# ST_Link_v2_1.net
KiCad netlist of a schematic drawn in EasyEDA Pro
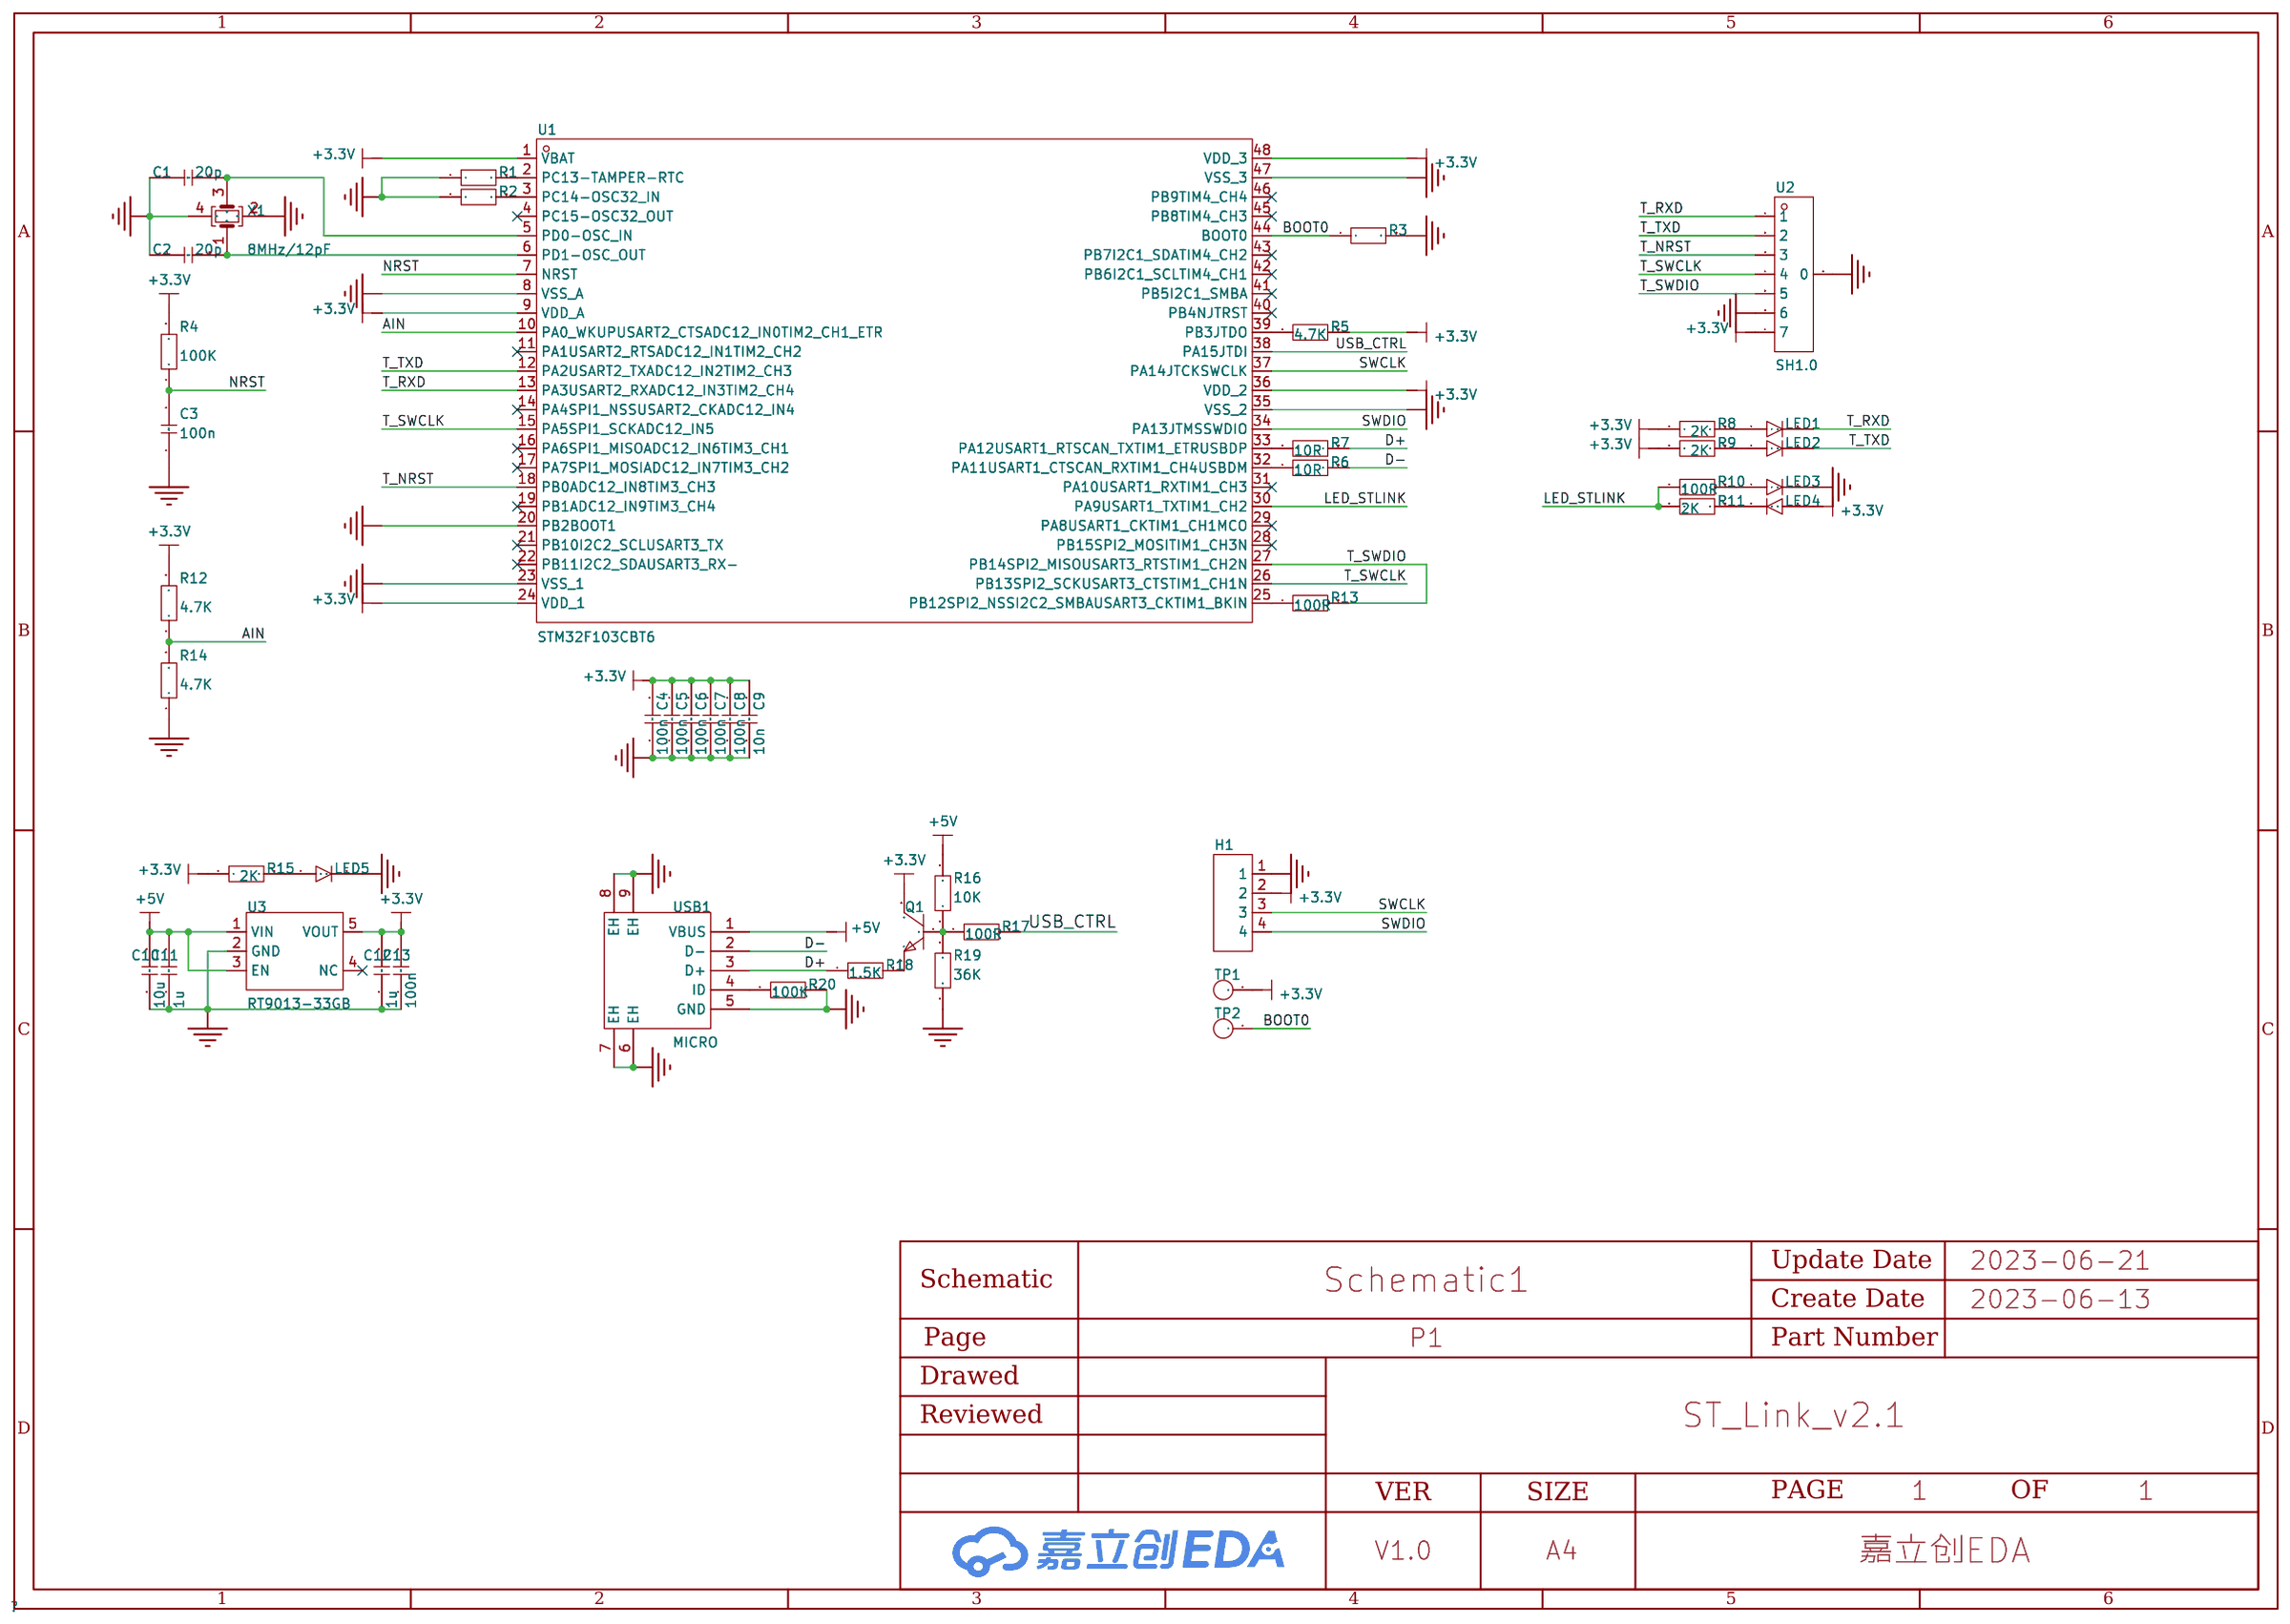
[diagram p0: schematic sheet]

(export (version "E")
  (design (tool "Eeschema 10.0.6"))
  (components
    (comp (ref "C1")
      (value "20p")
      (footprint "easyedapro:C0402")
      (libsource (lib "easyedapro") (part "C0402"))
    )
    (comp (ref "C2")
      (value "20p")
      (footprint "easyedapro:C0402")
      (libsource (lib "easyedapro") (part "C0402"))
    )
    (comp (ref "C3")
      (value "100n")
      (footprint "easyedapro:C0402")
      (libsource (lib "easyedapro") (part "C0402"))
    )
    (comp (ref "C4")
      (value "100n")
      (footprint "easyedapro:C0402")
      (libsource (lib "easyedapro") (part "C0402"))
    )
    (comp (ref "C5")
      (value "100n")
      (footprint "easyedapro:C0402")
      (libsource (lib "easyedapro") (part "C0402"))
    )
    (comp (ref "C6")
      (value "100n")
      (footprint "easyedapro:C0402")
      (libsource (lib "easyedapro") (part "C0402"))
    )
    (comp (ref "C7")
      (value "100n")
      (footprint "easyedapro:C0402")
      (libsource (lib "easyedapro") (part "C0402"))
    )
    (comp (ref "C8")
      (value "100n")
      (footprint "easyedapro:C0402")
      (libsource (lib "easyedapro") (part "C0402"))
    )
    (comp (ref "C9")
      (value "10n")
      (footprint "easyedapro:C0402")
      (libsource (lib "easyedapro") (part "C0402"))
    )
    (comp (ref "C10")
      (value "10u")
      (footprint "easyedapro:C0402")
      (libsource (lib "easyedapro") (part "C0402"))
    )
    (comp (ref "C11")
      (value "1u")
      (footprint "easyedapro:C0402")
      (libsource (lib "easyedapro") (part "C0402"))
    )
    (comp (ref "C12")
      (value "1u")
      (footprint "easyedapro:C0402")
      (libsource (lib "easyedapro") (part "C0402"))
    )
    (comp (ref "C13")
      (value "100n")
      (footprint "easyedapro:C0402")
      (libsource (lib "easyedapro") (part "C0402"))
    )
    (comp (ref "H1")
      (value "~")
      (footprint "easyedapro:PIN_1.27_1x4")
      (libsource (lib "easyedapro") (part "PIN_1.27_1x4"))
    )
    (comp (ref "LED1")
      (value "red")
      (footprint "easyedapro:LED0402")
      (libsource (lib "easyedapro") (part "LED-R-0402"))
    )
    (comp (ref "LED2")
      (value "green")
      (footprint "easyedapro:LED0402")
      (libsource (lib "easyedapro") (part "LED-G-0402"))
    )
    (comp (ref "LED3")
      (value "red")
      (footprint "easyedapro:LED0402")
      (libsource (lib "easyedapro") (part "LED-R-0402"))
    )
    (comp (ref "LED4")
      (value "green")
      (footprint "easyedapro:LED0402")
      (libsource (lib "easyedapro") (part "LED-G-0402"))
    )
    (comp (ref "LED5")
      (value "red")
      (footprint "easyedapro:LED0402")
      (libsource (lib "easyedapro") (part "LED-R-0402"))
    )
    (comp (ref "Q1")
      (value "~")
      (footprint "easyedapro:S8050_SOT-23")
      (libsource (lib "easyedapro") (part "NPN"))
    )
    (comp (ref "R1")
      (value "10K")
      (footprint "easyedapro:R0402")
      (libsource (lib "easyedapro") (part "R0402"))
    )
    (comp (ref "R2")
      (value "10K")
      (footprint "easyedapro:R0402")
      (libsource (lib "easyedapro") (part "R0402"))
    )
    (comp (ref "R3")
      (value "10K")
      (footprint "easyedapro:R0402")
      (libsource (lib "easyedapro") (part "R0402"))
    )
    (comp (ref "R4")
      (value "100K")
      (footprint "easyedapro:R0402")
      (libsource (lib "easyedapro") (part "R0402"))
    )
    (comp (ref "R5")
      (value "4.7K")
      (footprint "easyedapro:R0402")
      (libsource (lib "easyedapro") (part "R0402"))
    )
    (comp (ref "R6")
      (value "10R")
      (footprint "easyedapro:R0402")
      (libsource (lib "easyedapro") (part "R0402"))
    )
    (comp (ref "R7")
      (value "10R")
      (footprint "easyedapro:R0402")
      (libsource (lib "easyedapro") (part "R0402"))
    )
    (comp (ref "R8")
      (value "2K")
      (footprint "easyedapro:R0402")
      (libsource (lib "easyedapro") (part "R0402"))
    )
    (comp (ref "R9")
      (value "2K")
      (footprint "easyedapro:R0402")
      (libsource (lib "easyedapro") (part "R0402"))
    )
    (comp (ref "R10")
      (value "100R")
      (footprint "easyedapro:R0402")
      (libsource (lib "easyedapro") (part "R0402"))
    )
    (comp (ref "R11")
      (value "2K")
      (footprint "easyedapro:R0402")
      (libsource (lib "easyedapro") (part "R0402"))
    )
    (comp (ref "R12")
      (value "4.7K")
      (footprint "easyedapro:R0402")
      (libsource (lib "easyedapro") (part "R0402"))
    )
    (comp (ref "R13")
      (value "100R")
      (footprint "easyedapro:R0402")
      (libsource (lib "easyedapro") (part "R0402"))
    )
    (comp (ref "R14")
      (value "4.7K")
      (footprint "easyedapro:R0402")
      (libsource (lib "easyedapro") (part "R0402"))
    )
    (comp (ref "R15")
      (value "2K")
      (footprint "easyedapro:R0402")
      (libsource (lib "easyedapro") (part "R0402"))
    )
    (comp (ref "R16")
      (value "10K")
      (footprint "easyedapro:R0402")
      (libsource (lib "easyedapro") (part "R0402"))
    )
    (comp (ref "R17")
      (value "100R")
      (footprint "easyedapro:R0402")
      (libsource (lib "easyedapro") (part "R0402"))
    )
    (comp (ref "R18")
      (value "1.5K")
      (footprint "easyedapro:R0402")
      (libsource (lib "easyedapro") (part "R0402"))
    )
    (comp (ref "R19")
      (value "36K")
      (footprint "easyedapro:R0402")
      (libsource (lib "easyedapro") (part "R0402"))
    )
    (comp (ref "R20")
      (value "100K")
      (footprint "easyedapro:R0402")
      (libsource (lib "easyedapro") (part "R0402"))
    )
    (comp (ref "TP1")
      (value "~")
      (footprint "easyedapro:TP-1.27")
      (libsource (lib "easyedapro") (part "TP-1.27"))
    )
    (comp (ref "TP2")
      (value "~")
      (footprint "easyedapro:TP-1.27")
      (libsource (lib "easyedapro") (part "TP-1.27"))
    )
    (comp (ref "U1")
      (value "STM32F103CBT6")
      (footprint "easyedapro:LQFP-48_L7.0-W7.0-P0.50-LS9.0-BL")
      (fields (field (name "Manufacturer") "ST(意法半导体)"))
      (libsource (lib "easyedapro") (part "STM32F103CBT6"))
    )
    (comp (ref "U2")
      (value "SH1.0")
      (footprint "easyedapro:CONN-SMD_7P-SH1.00-7P-WT")
      (libsource (lib "easyedapro") (part "SH1.0_7P"))
    )
    (comp (ref "U3")
      (value "RT9013-33GB")
      (footprint "easyedapro:SOT-23-5_L3.0-W1.7-P0.95-LS2.8-BL")
      (description "输出类型:固定;输出极性:正;最大输入电压:5.5V;输出电压:3.3V;输出电流:500mA;电源纹波抑制比(PSRR):50dB@(10kHz);")
      (fields (field (name "Manufacturer") "RICHTEK(立锜)"))
      (libsource (lib "easyedapro") (part "RT9013-33GB"))
    )
    (comp (ref "USB1")
      (value "MICRO")
      (footprint "easyedapro:MICRO-USB-SMD_KH-MICRO-SMT.J7.2-5P")
      (description "连接器类型:Micro-B;标准:USB 2.0;公母:母座;触点数量:5;端口数量:1;安装方式:卧贴;额定电流 - 电源:1A;工作温度范围:-30°C~+80°C;")
      (fields (field (name "Manufacturer") "kinghelm(金航标)"))
      (libsource (lib "easyedapro") (part "KH-MICRO-SMT.J7.2-5P"))
    )
    (comp (ref "X1")
      (value "8MHz/12pF")
      (footprint "easyedapro:OSC-SMD_4P-L3.2-W2.5-BL")
      (fields (field (name "Manufacturer Part") "X322516MLB4SI") (field (name "Manufacturer") "YXC(扬兴晶振)"))
      (libsource (lib "easyedapro") (part "OSC3225"))
    )
  )
  (nets
    (net (code "1") (name "+3.3V") (class "Default")
      (node (ref "C12") (pin "2") (pinfunction "2_2") (pintype "input"))
      (node (ref "C13") (pin "2") (pinfunction "2_2") (pintype "input"))
      (node (ref "C4") (pin "2") (pinfunction "2_2") (pintype "input"))
      (node (ref "C5") (pin "2") (pinfunction "2_2") (pintype "input"))
      (node (ref "C6") (pin "2") (pinfunction "2_2") (pintype "input"))
      (node (ref "C7") (pin "2") (pinfunction "2_2") (pintype "input"))
      (node (ref "C8") (pin "2") (pinfunction "2_2") (pintype "input"))
      (node (ref "C9") (pin "2") (pinfunction "2_2") (pintype "input"))
      (node (ref "H1") (pin "2") (pinfunction "2_2") (pintype "input"))
      (node (ref "LED4") (pin "1") (pinfunction "1_1") (pintype "input"))
      (node (ref "Q1") (pin "3") (pinfunction "3_3") (pintype "unspecified"))
      (node (ref "R12") (pin "2") (pinfunction "2_2") (pintype "input"))
      (node (ref "R15") (pin "1") (pinfunction "1_1") (pintype "input"))
      (node (ref "R4") (pin "2") (pinfunction "2_2") (pintype "input"))
      (node (ref "R5") (pin "2") (pinfunction "2_2") (pintype "input"))
      (node (ref "R8") (pin "1") (pinfunction "1_1") (pintype "input"))
      (node (ref "R9") (pin "1") (pinfunction "1_1") (pintype "input"))
      (node (ref "TP1") (pin "1") (pinfunction "1_1") (pintype "input"))
      (node (ref "U1") (pin "1") (pinfunction "VBAT_1") (pintype "input"))
      (node (ref "U1") (pin "24") (pinfunction "VDD_1_24") (pintype "input"))
      (node (ref "U1") (pin "36") (pinfunction "VDD_2_36") (pintype "input"))
      (node (ref "U1") (pin "48") (pinfunction "VDD_3_48") (pintype "input"))
      (node (ref "U1") (pin "9") (pinfunction "VDD_A_9") (pintype "input"))
      (node (ref "U2") (pin "7") (pinfunction "7_7") (pintype "input"))
      (node (ref "U3") (pin "5") (pinfunction "VOUT_5") (pintype "input"))
    )
    (net (code "2") (name "+5V") (class "Default")
      (node (ref "C10") (pin "2") (pinfunction "2_2") (pintype "input"))
      (node (ref "C11") (pin "2") (pinfunction "2_2") (pintype "input"))
      (node (ref "R16") (pin "2") (pinfunction "2_2") (pintype "input"))
      (node (ref "U3") (pin "1") (pinfunction "VIN_1") (pintype "input"))
      (node (ref "U3") (pin "3") (pinfunction "EN_3") (pintype "input"))
      (node (ref "USB1") (pin "1") (pinfunction "VBUS_1") (pintype "input"))
    )
    (net (code "3") (name "/AIN") (class "Default")
      (node (ref "R12") (pin "1") (pinfunction "1_1") (pintype "input"))
      (node (ref "R14") (pin "2") (pinfunction "2_2") (pintype "input"))
      (node (ref "U1") (pin "10") (pinfunction "PA0_WKUPUSART2_CTSADC12_IN0TIM2_CH1_ETR_10") (pintype "input"))
    )
    (net (code "4") (name "/BOOT0") (class "Default")
      (node (ref "R3") (pin "1") (pinfunction "1_1") (pintype "input"))
      (node (ref "TP2") (pin "1") (pinfunction "1_1") (pintype "input"))
      (node (ref "U1") (pin "44") (pinfunction "BOOT0_44") (pintype "input"))
    )
    (net (code "5") (name "/D+") (class "Default")
      (node (ref "R18") (pin "1") (pinfunction "1_1") (pintype "input"))
      (node (ref "R7") (pin "2") (pinfunction "2_2") (pintype "input"))
      (node (ref "USB1") (pin "3") (pinfunction "D+_3") (pintype "input"))
    )
    (net (code "6") (name "/D-") (class "Default")
      (node (ref "R6") (pin "2") (pinfunction "2_2") (pintype "input"))
      (node (ref "USB1") (pin "2") (pinfunction "D-_2") (pintype "input"))
    )
    (net (code "7") (name "/LED_STLINK") (class "Default")
      (node (ref "R10") (pin "1") (pinfunction "1_1") (pintype "input"))
      (node (ref "R11") (pin "1") (pinfunction "1_1") (pintype "input"))
      (node (ref "U1") (pin "30") (pinfunction "PA9USART1_TXTIM1_CH2_30") (pintype "input"))
    )
    (net (code "8") (name "/NRST") (class "Default")
      (node (ref "C3") (pin "2") (pinfunction "2_2") (pintype "input"))
      (node (ref "R4") (pin "1") (pinfunction "1_1") (pintype "input"))
      (node (ref "U1") (pin "7") (pinfunction "NRST_7") (pintype "input"))
    )
    (net (code "9") (name "/SWCLK") (class "Default")
      (node (ref "H1") (pin "3") (pinfunction "3_3") (pintype "input"))
      (node (ref "U1") (pin "37") (pinfunction "PA14JTCKSWCLK_37") (pintype "input"))
    )
    (net (code "10") (name "/SWDIO") (class "Default")
      (node (ref "H1") (pin "4") (pinfunction "4_4") (pintype "input"))
      (node (ref "U1") (pin "34") (pinfunction "PA13JTMSSWDIO_34") (pintype "input"))
    )
    (net (code "11") (name "/T_NRST") (class "Default")
      (node (ref "U1") (pin "18") (pinfunction "PB0ADC12_IN8TIM3_CH3_18") (pintype "input"))
      (node (ref "U2") (pin "3") (pinfunction "3_3") (pintype "input"))
    )
    (net (code "12") (name "/T_RXD") (class "Default")
      (node (ref "LED1") (pin "2") (pinfunction "2_2") (pintype "input"))
      (node (ref "U1") (pin "13") (pinfunction "PA3USART2_RXADC12_IN3TIM2_CH4_13") (pintype "input"))
      (node (ref "U2") (pin "1") (pinfunction "1_1") (pintype "input"))
    )
    (net (code "13") (name "/T_SWCLK") (class "Default")
      (node (ref "U1") (pin "15") (pinfunction "PA5SPI1_SCKADC12_IN5_15") (pintype "input"))
      (node (ref "U1") (pin "26") (pinfunction "PB13SPI2_SCKUSART3_CTSTIM1_CH1N_26") (pintype "input"))
      (node (ref "U2") (pin "4") (pinfunction "4_4") (pintype "input"))
    )
    (net (code "14") (name "/T_SWDIO") (class "Default")
      (node (ref "R13") (pin "2") (pinfunction "2_2") (pintype "input"))
      (node (ref "U1") (pin "27") (pinfunction "PB14SPI2_MISOUSART3_RTSTIM1_CH2N_27") (pintype "input"))
      (node (ref "U2") (pin "5") (pinfunction "5_5") (pintype "input"))
    )
    (net (code "15") (name "/T_TXD") (class "Default")
      (node (ref "LED2") (pin "2") (pinfunction "2_2") (pintype "input"))
      (node (ref "U1") (pin "12") (pinfunction "PA2USART2_TXADC12_IN2TIM2_CH3_12") (pintype "input"))
      (node (ref "U2") (pin "2") (pinfunction "2_2") (pintype "input"))
    )
    (net (code "16") (name "/USB_CTRL") (class "Default")
      (node (ref "R17") (pin "2") (pinfunction "2_2") (pintype "input"))
      (node (ref "U1") (pin "38") (pinfunction "PA15JTDI_38") (pintype "input"))
    )
    (net (code "17") (name "GND") (class "Default")
      (node (ref "C1") (pin "1") (pinfunction "1_1") (pintype "input"))
      (node (ref "C10") (pin "1") (pinfunction "1_1") (pintype "input"))
      (node (ref "C11") (pin "1") (pinfunction "1_1") (pintype "input"))
      (node (ref "C12") (pin "1") (pinfunction "1_1") (pintype "input"))
      (node (ref "C13") (pin "1") (pinfunction "1_1") (pintype "input"))
      (node (ref "C2") (pin "1") (pinfunction "1_1") (pintype "input"))
      (node (ref "C3") (pin "1") (pinfunction "1_1") (pintype "input"))
      (node (ref "C4") (pin "1") (pinfunction "1_1") (pintype "input"))
      (node (ref "C5") (pin "1") (pinfunction "1_1") (pintype "input"))
      (node (ref "C6") (pin "1") (pinfunction "1_1") (pintype "input"))
      (node (ref "C7") (pin "1") (pinfunction "1_1") (pintype "input"))
      (node (ref "C8") (pin "1") (pinfunction "1_1") (pintype "input"))
      (node (ref "C9") (pin "1") (pinfunction "1_1") (pintype "input"))
      (node (ref "H1") (pin "1") (pinfunction "1_1") (pintype "input"))
      (node (ref "LED3") (pin "2") (pinfunction "2_2") (pintype "input"))
      (node (ref "LED5") (pin "2") (pinfunction "2_2") (pintype "input"))
      (node (ref "R1") (pin "1") (pinfunction "1_1") (pintype "input"))
      (node (ref "R14") (pin "1") (pinfunction "1_1") (pintype "input"))
      (node (ref "R19") (pin "1") (pinfunction "1_1") (pintype "input"))
      (node (ref "R2") (pin "1") (pinfunction "1_1") (pintype "input"))
      (node (ref "R20") (pin "2") (pinfunction "2_2") (pintype "input"))
      (node (ref "R3") (pin "2") (pinfunction "2_2") (pintype "input"))
      (node (ref "U1") (pin "20") (pinfunction "PB2BOOT1_20") (pintype "input"))
      (node (ref "U1") (pin "23") (pinfunction "VSS_1_23") (pintype "input"))
      (node (ref "U1") (pin "35") (pinfunction "VSS_2_35") (pintype "input"))
      (node (ref "U1") (pin "47") (pinfunction "VSS_3_47") (pintype "input"))
      (node (ref "U1") (pin "8") (pinfunction "VSS_A_8") (pintype "input"))
      (node (ref "U2") (pin "0") (pinfunction "0_0") (pintype "input"))
      (node (ref "U2") (pin "6") (pinfunction "6_6") (pintype "input"))
      (node (ref "U3") (pin "2") (pinfunction "GND_2") (pintype "input"))
      (node (ref "USB1") (pin "5") (pinfunction "GND_5") (pintype "input"))
      (node (ref "USB1") (pin "6") (pinfunction "EH_6") (pintype "input"))
      (node (ref "USB1") (pin "7") (pinfunction "EH_7") (pintype "input"))
      (node (ref "USB1") (pin "8") (pinfunction "EH_8") (pintype "input"))
      (node (ref "USB1") (pin "9") (pinfunction "EH_9") (pintype "input"))
      (node (ref "X1") (pin "2") (pinfunction "GND_2") (pintype "input"))
      (node (ref "X1") (pin "4") (pinfunction "GND_4") (pintype "input"))
    )
    (net (code "18") (name "Net-(LED1-Pad1)") (class "Default")
      (node (ref "LED1") (pin "1") (pinfunction "1_1") (pintype "input"))
      (node (ref "R8") (pin "2") (pinfunction "2_2") (pintype "input"))
    )
    (net (code "19") (name "Net-(LED2-Pad1)") (class "Default")
      (node (ref "LED2") (pin "1") (pinfunction "1_1") (pintype "input"))
      (node (ref "R9") (pin "2") (pinfunction "2_2") (pintype "input"))
    )
    (net (code "20") (name "Net-(LED3-Pad1)") (class "Default")
      (node (ref "LED3") (pin "1") (pinfunction "1_1") (pintype "input"))
      (node (ref "R10") (pin "2") (pinfunction "2_2") (pintype "input"))
    )
    (net (code "21") (name "Net-(LED4-Pad2)") (class "Default")
      (node (ref "LED4") (pin "2") (pinfunction "2_2") (pintype "input"))
      (node (ref "R11") (pin "2") (pinfunction "2_2") (pintype "input"))
    )
    (net (code "22") (name "Net-(LED5-Pad1)") (class "Default")
      (node (ref "LED5") (pin "1") (pinfunction "1_1") (pintype "input"))
      (node (ref "R15") (pin "2") (pinfunction "2_2") (pintype "input"))
    )
    (net (code "23") (name "Net-(Q1-Pad1)") (class "Default")
      (node (ref "Q1") (pin "1") (pinfunction "1_1") (pintype "unspecified"))
      (node (ref "R16") (pin "1") (pinfunction "1_1") (pintype "input"))
      (node (ref "R17") (pin "1") (pinfunction "1_1") (pintype "input"))
      (node (ref "R19") (pin "2") (pinfunction "2_2") (pintype "input"))
    )
    (net (code "24") (name "Net-(Q1-Pad2)") (class "Default")
      (node (ref "Q1") (pin "2") (pinfunction "2_2") (pintype "unspecified"))
      (node (ref "R18") (pin "2") (pinfunction "2_2") (pintype "input"))
    )
    (net (code "25") (name "Net-(U1-PA11USART1_CTSCAN_RXTIM1_CH4USBDM)") (class "Default")
      (node (ref "R6") (pin "1") (pinfunction "1_1") (pintype "input"))
      (node (ref "U1") (pin "32") (pinfunction "PA11USART1_CTSCAN_RXTIM1_CH4USBDM_32") (pintype "input"))
    )
    (net (code "26") (name "Net-(U1-PA12USART1_RTSCAN_TXTIM1_ETRUSBDP)") (class "Default")
      (node (ref "R7") (pin "1") (pinfunction "1_1") (pintype "input"))
      (node (ref "U1") (pin "33") (pinfunction "PA12USART1_RTSCAN_TXTIM1_ETRUSBDP_33") (pintype "input"))
    )
    (net (code "27") (name "Net-(U1-PB3JTDO)") (class "Default")
      (node (ref "R5") (pin "1") (pinfunction "1_1") (pintype "input"))
      (node (ref "U1") (pin "39") (pinfunction "PB3JTDO_39") (pintype "input"))
    )
    (net (code "28") (name "Net-(U1-PB12SPI2_NSSI2C2_SMBAUSART3_CKTIM1_BKIN)") (class "Default")
      (node (ref "R13") (pin "1") (pinfunction "1_1") (pintype "input"))
      (node (ref "U1") (pin "25") (pinfunction "PB12SPI2_NSSI2C2_SMBAUSART3_CKTIM1_BKIN_25") (pintype "input"))
    )
    (net (code "29") (name "Net-(U1-PC13-TAMPER-RTC)") (class "Default")
      (node (ref "R1") (pin "2") (pinfunction "2_2") (pintype "input"))
      (node (ref "U1") (pin "2") (pinfunction "PC13-TAMPER-RTC_2") (pintype "input"))
    )
    (net (code "30") (name "Net-(U1-PC14-OSC32_IN)") (class "Default")
      (node (ref "R2") (pin "2") (pinfunction "2_2") (pintype "input"))
      (node (ref "U1") (pin "3") (pinfunction "PC14-OSC32_IN_3") (pintype "input"))
    )
    (net (code "31") (name "Net-(U1-PD0-OSC_IN)") (class "Default")
      (node (ref "C1") (pin "2") (pinfunction "2_2") (pintype "input"))
      (node (ref "U1") (pin "5") (pinfunction "PD0-OSC_IN_5") (pintype "input"))
      (node (ref "X1") (pin "3") (pinfunction "OSC2_3") (pintype "input"))
    )
    (net (code "32") (name "Net-(U1-PD1-OSC_OUT)") (class "Default")
      (node (ref "C2") (pin "2") (pinfunction "2_2") (pintype "input"))
      (node (ref "U1") (pin "6") (pinfunction "PD1-OSC_OUT_6") (pintype "input"))
      (node (ref "X1") (pin "1") (pinfunction "OSC1_1") (pintype "input"))
    )
    (net (code "33") (name "Net-(USB1-ID)") (class "Default")
      (node (ref "R20") (pin "1") (pinfunction "1_1") (pintype "input"))
      (node (ref "USB1") (pin "4") (pinfunction "ID_4") (pintype "input"))
    )
    (net (code "34") (name "unconnected-(U1-PA1USART2_RTSADC12_IN1TIM2_CH2-Pad11)") (class "Default")
      (node (ref "U1") (pin "11") (pinfunction "PA1USART2_RTSADC12_IN1TIM2_CH2_11") (pintype "input+no_connect"))
    )
    (net (code "35") (name "unconnected-(U1-PA4SPI1_NSSUSART2_CKADC12_IN4-Pad14)") (class "Default")
      (node (ref "U1") (pin "14") (pinfunction "PA4SPI1_NSSUSART2_CKADC12_IN4_14") (pintype "input+no_connect"))
    )
    (net (code "36") (name "unconnected-(U1-PA6SPI1_MISOADC12_IN6TIM3_CH1-Pad16)") (class "Default")
      (node (ref "U1") (pin "16") (pinfunction "PA6SPI1_MISOADC12_IN6TIM3_CH1_16") (pintype "input+no_connect"))
    )
    (net (code "37") (name "unconnected-(U1-PA7SPI1_MOSIADC12_IN7TIM3_CH2-Pad17)") (class "Default")
      (node (ref "U1") (pin "17") (pinfunction "PA7SPI1_MOSIADC12_IN7TIM3_CH2_17") (pintype "input+no_connect"))
    )
    (net (code "38") (name "unconnected-(U1-PA8USART1_CKTIM1_CH1MCO-Pad29)") (class "Default")
      (node (ref "U1") (pin "29") (pinfunction "PA8USART1_CKTIM1_CH1MCO_29") (pintype "input+no_connect"))
    )
    (net (code "39") (name "unconnected-(U1-PA10USART1_RXTIM1_CH3-Pad31)") (class "Default")
      (node (ref "U1") (pin "31") (pinfunction "PA10USART1_RXTIM1_CH3_31") (pintype "input+no_connect"))
    )
    (net (code "40") (name "unconnected-(U1-PB1ADC12_IN9TIM3_CH4-Pad19)") (class "Default")
      (node (ref "U1") (pin "19") (pinfunction "PB1ADC12_IN9TIM3_CH4_19") (pintype "input+no_connect"))
    )
    (net (code "41") (name "unconnected-(U1-PB4NJTRST-Pad40)") (class "Default")
      (node (ref "U1") (pin "40") (pinfunction "PB4NJTRST_40") (pintype "input+no_connect"))
    )
    (net (code "42") (name "unconnected-(U1-PB5I2C1_SMBA-Pad41)") (class "Default")
      (node (ref "U1") (pin "41") (pinfunction "PB5I2C1_SMBA_41") (pintype "input+no_connect"))
    )
    (net (code "43") (name "unconnected-(U1-PB6I2C1_SCLTIM4_CH1-Pad42)") (class "Default")
      (node (ref "U1") (pin "42") (pinfunction "PB6I2C1_SCLTIM4_CH1_42") (pintype "input+no_connect"))
    )
    (net (code "44") (name "unconnected-(U1-PB7I2C1_SDATIM4_CH2-Pad43)") (class "Default")
      (node (ref "U1") (pin "43") (pinfunction "PB7I2C1_SDATIM4_CH2_43") (pintype "input+no_connect"))
    )
    (net (code "45") (name "unconnected-(U1-PB8TIM4_CH3-Pad45)") (class "Default")
      (node (ref "U1") (pin "45") (pinfunction "PB8TIM4_CH3_45") (pintype "input+no_connect"))
    )
    (net (code "46") (name "unconnected-(U1-PB9TIM4_CH4-Pad46)") (class "Default")
      (node (ref "U1") (pin "46") (pinfunction "PB9TIM4_CH4_46") (pintype "input+no_connect"))
    )
    (net (code "47") (name "unconnected-(U1-PB10I2C2_SCLUSART3_TX-Pad21)") (class "Default")
      (node (ref "U1") (pin "21") (pinfunction "PB10I2C2_SCLUSART3_TX_21") (pintype "input+no_connect"))
    )
    (net (code "48") (name "unconnected-(U1-PB11I2C2_SDAUSART3_RX--Pad22)") (class "Default")
      (node (ref "U1") (pin "22") (pinfunction "PB11I2C2_SDAUSART3_RX-_22") (pintype "input+no_connect"))
    )
    (net (code "49") (name "unconnected-(U1-PB15SPI2_MOSITIM1_CH3N-Pad28)") (class "Default")
      (node (ref "U1") (pin "28") (pinfunction "PB15SPI2_MOSITIM1_CH3N_28") (pintype "input+no_connect"))
    )
    (net (code "50") (name "unconnected-(U1-PC15-OSC32_OUT-Pad4)") (class "Default")
      (node (ref "U1") (pin "4") (pinfunction "PC15-OSC32_OUT_4") (pintype "input+no_connect"))
    )
    (net (code "51") (name "unconnected-(U3-NC-Pad4)") (class "Default")
      (node (ref "U3") (pin "4") (pinfunction "NC_4") (pintype "input+no_connect"))
    )
  )
)
